# MT_Relay_switch.net
KiCad netlist of a schematic drawn in EAGLE
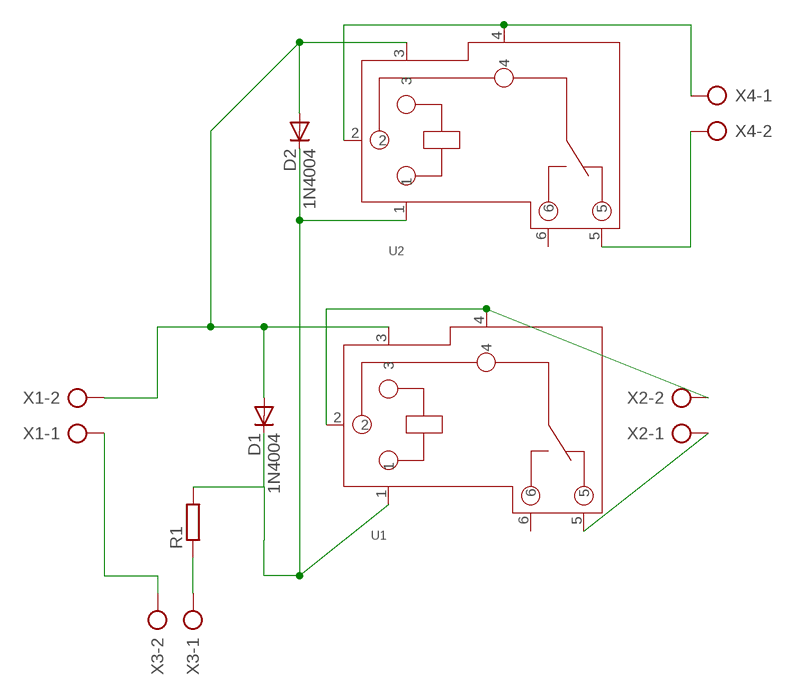
[diagram p0: schematic, sheet 1]

(export (version "E")
  (design (tool "Eeschema 10.0.6"))
  (components
    (comp (ref "D1")
      (value "1N4004")
      (footprint "eagle-import:DO41-10")
      (libsource (lib "eagle-import") (part "1N4004"))
    )
    (comp (ref "D2")
      (value "1N4004")
      (footprint "eagle-import:DO41-10")
      (libsource (lib "eagle-import") (part "1N4004"))
    )
    (comp (ref "R1")
      (value "R-EU_0204/7")
      (footprint "eagle-import:0204_7")
      (libsource (lib "eagle-import") (part "R-EU_0204/7"))
    )
    (comp (ref "U1")
      (value "RELAY-SLA-05VDC-SL-C")
      (footprint "eagle-import:6P-19.8H")
      (libsource (lib "eagle-import") (part "RELAY-SLA-05VDC-SL-C"))
    )
    (comp (ref "U2")
      (value "RELAY-SLA-05VDC-SL-C")
      (footprint "eagle-import:6P-19.8H")
      (libsource (lib "eagle-import") (part "RELAY-SLA-05VDC-SL-C"))
    )
    (comp (ref "X1")
      (value "AK300/2")
      (footprint "eagle-import:AK300_2")
      (libsource (lib "eagle-import") (part "AK300/2"))
    )
    (comp (ref "X2")
      (value "AK300/2")
      (footprint "eagle-import:AK300_2")
      (libsource (lib "eagle-import") (part "AK300/2"))
    )
    (comp (ref "X3")
      (value "AK300/2")
      (footprint "eagle-import:AK300_2")
      (libsource (lib "eagle-import") (part "AK300/2"))
    )
    (comp (ref "X4")
      (value "AK300/2")
      (footprint "eagle-import:AK300_2")
      (libsource (lib "eagle-import") (part "AK300/2"))
    )
  )
  (nets
    (net (code "1") (name "Net-(D1-PadC)") (class "Default")
      (node (ref "D1") (pin "C") (pinfunction "C_C") (pintype "passive"))
      (node (ref "D2") (pin "C") (pinfunction "C_C") (pintype "passive"))
      (node (ref "R1") (pin "2") (pinfunction "2_2") (pintype "passive"))
      (node (ref "U1") (pin "1") (pinfunction "1_1") (pintype "bidirectional"))
      (node (ref "U2") (pin "1") (pinfunction "1_1") (pintype "bidirectional"))
    )
    (net (code "2") (name "Net-(X1A-KL)") (class "Default")
      (node (ref "X1") (pin "1") (pinfunction "KL_1") (pintype "passive"))
      (node (ref "X3") (pin "2") (pinfunction "KL_2") (pintype "passive"))
    )
    (net (code "3") (name "Net-(X1B-KL)") (class "Default")
      (node (ref "D1") (pin "A") (pinfunction "A_A") (pintype "passive"))
      (node (ref "D2") (pin "A") (pinfunction "A_A") (pintype "passive"))
      (node (ref "U1") (pin "3") (pinfunction "3_3") (pintype "bidirectional"))
      (node (ref "U2") (pin "3") (pinfunction "3_3") (pintype "bidirectional"))
      (node (ref "X1") (pin "2") (pinfunction "KL_2") (pintype "passive"))
    )
    (net (code "4") (name "Net-(X2A-KL)") (class "Default")
      (node (ref "U1") (pin "5") (pinfunction "5_5") (pintype "bidirectional"))
      (node (ref "X2") (pin "1") (pinfunction "KL_1") (pintype "passive"))
    )
    (net (code "5") (name "Net-(X2B-KL)") (class "Default")
      (node (ref "U1") (pin "2") (pinfunction "2_2") (pintype "bidirectional"))
      (node (ref "U1") (pin "4") (pinfunction "4_4") (pintype "bidirectional"))
      (node (ref "X2") (pin "2") (pinfunction "KL_2") (pintype "passive"))
    )
    (net (code "6") (name "Net-(X3A-KL)") (class "Default")
      (node (ref "R1") (pin "1") (pinfunction "1_1") (pintype "passive"))
      (node (ref "X3") (pin "1") (pinfunction "KL_1") (pintype "passive"))
    )
    (net (code "7") (name "Net-(X4A-KL)") (class "Default")
      (node (ref "U2") (pin "2") (pinfunction "2_2") (pintype "bidirectional"))
      (node (ref "U2") (pin "4") (pinfunction "4_4") (pintype "bidirectional"))
      (node (ref "X4") (pin "1") (pinfunction "KL_1") (pintype "passive"))
    )
    (net (code "8") (name "Net-(X4B-KL)") (class "Default")
      (node (ref "U2") (pin "5") (pinfunction "5_5") (pintype "bidirectional"))
      (node (ref "X4") (pin "2") (pinfunction "KL_2") (pintype "passive"))
    )
    (net (code "9") (name "unconnected-(U1-Pad6)") (class "Default")
      (node (ref "U1") (pin "6") (pinfunction "6_6") (pintype "bidirectional"))
    )
    (net (code "10") (name "unconnected-(U2-Pad6)") (class "Default")
      (node (ref "U2") (pin "6") (pinfunction "6_6") (pintype "bidirectional"))
    )
  )
)
